# IC_VCE.net
KiCad netlist of a schematic drawn in Altium Designer
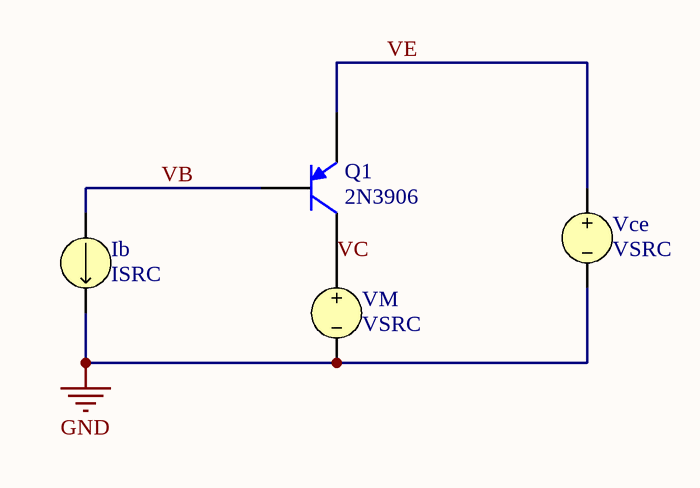
[diagram p0: IC_VCE.SchDoc]

(export (version "E")
  (design (tool "Eeschema 10.0.6"))
  (components
    (comp (ref "Ib")
      (value "ISRC")
      (description "Current Source")
      (fields (field (name "PUBLISHER") "Altium Limited"))
      (libsource (lib "Simulation Sources") (part "ISRC"))
    )
    (comp (ref "Q1")
      (value "2N3906")
      (footprint "TO-92A")
      (description "PNP General Purpose Amplifier")
      (fields (field (name "PUBLISHER") "Altium Limited"))
      (libsource (lib "Miscellaneous Devices") (part "2N3906"))
    )
    (comp (ref "Vce")
      (value "VSRC")
      (description "Voltage Source")
      (fields (field (name "PUBLISHER") "Altium Limited"))
      (libsource (lib "Simulation Sources") (part "VSRC"))
    )
    (comp (ref "VM")
      (value "VSRC")
      (description "Voltage Source")
      (fields (field (name "PUBLISHER") "Altium Limited"))
      (libsource (lib "Simulation Sources") (part "VSRC"))
    )
  )
  (nets
    (net (code "1") (name "/VB") (class "Default")
      (node (ref "Ib") (pin "1") (pinfunction "1_1") (pintype "passive"))
      (node (ref "Q1") (pin "2") (pinfunction "B_2") (pintype "passive"))
    )
    (net (code "2") (name "/VC") (class "Default")
      (node (ref "Q1") (pin "3") (pinfunction "C_3") (pintype "passive"))
      (node (ref "VM") (pin "1") (pinfunction "1_1") (pintype "passive"))
    )
    (net (code "3") (name "/VE") (class "Default")
      (node (ref "Q1") (pin "1") (pinfunction "E_1") (pintype "passive"))
      (node (ref "Vce") (pin "1") (pinfunction "1_1") (pintype "passive"))
    )
    (net (code "4") (name "GND") (class "Default")
      (node (ref "Ib") (pin "2") (pinfunction "2_2") (pintype "passive"))
      (node (ref "VM") (pin "2") (pinfunction "2_2") (pintype "passive"))
      (node (ref "Vce") (pin "2") (pinfunction "2_2") (pintype "passive"))
    )
  )
)
